# 05_USART.net
KiCad netlist of a schematic drawn in Altium Designer
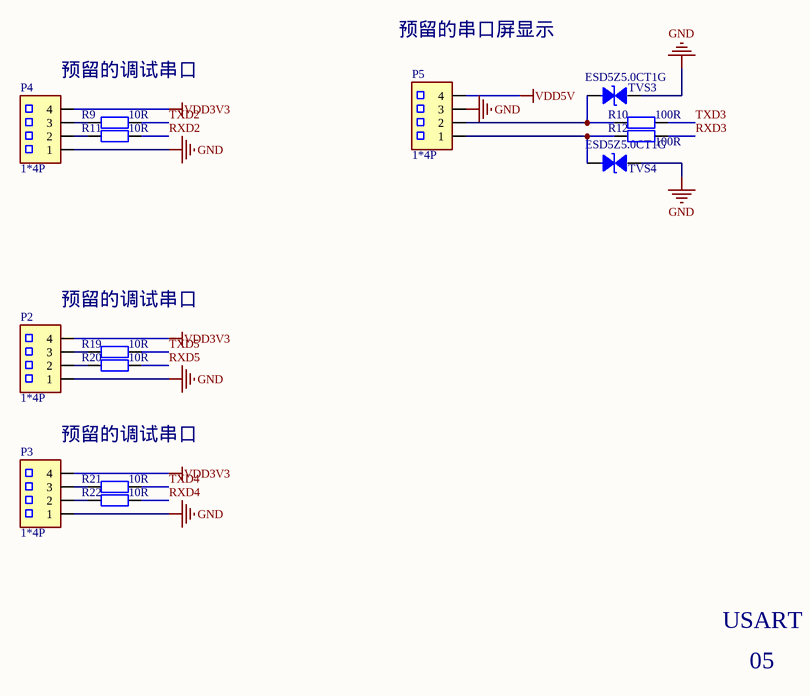
[diagram p0: 05_USART.SchDoc]

(export (version "E")
  (design (tool "Eeschema 10.0.6"))
  (components
    (comp (ref "P2") (value "1*4P") (footprint "XH2.54-4A") (libsource (lib "PARK-N5 V1.0") (part "HDR1*4")))
    (comp (ref "P3") (value "1*4P") (footprint "XH2.54-4A") (libsource (lib "PARK-N5 V1.0") (part "HDR1*4")))
    (comp (ref "P4") (value "1*4P") (footprint "XH2.54-4A") (libsource (lib "PARK-N5 V1.0") (part "HDR1*4")))
    (comp (ref "P5") (value "1*4P") (footprint "XH2.54-4A") (libsource (lib "PARK-N5 V1.0") (part "HDR1*4")))
    (comp (ref "R9")
      (value "10R")
      (footprint "SMD-0603")
      (description "贴片电阻 5%")
      (libsource (lib "XiaoyI") (part "RES2"))
    )
    (comp (ref "R10")
      (value "100R")
      (footprint "SMD-0603")
      (description "贴片电阻 5%")
      (libsource (lib "XiaoyI") (part "RES2"))
    )
    (comp (ref "R11")
      (value "10R")
      (footprint "SMD-0603")
      (description "贴片电阻 5%")
      (libsource (lib "XiaoyI") (part "RES2"))
    )
    (comp (ref "R12")
      (value "100R")
      (footprint "SMD-0603")
      (description "贴片电阻 5%")
      (libsource (lib "XiaoyI") (part "RES2"))
    )
    (comp (ref "R19")
      (value "10R")
      (footprint "SMD-0603")
      (description "贴片电阻 5%")
      (libsource (lib "XiaoyI") (part "RES2"))
    )
    (comp (ref "R20")
      (value "10R")
      (footprint "SMD-0603")
      (description "贴片电阻 5%")
      (libsource (lib "XiaoyI") (part "RES2"))
    )
    (comp (ref "R21")
      (value "10R")
      (footprint "SMD-0603")
      (description "贴片电阻 5%")
      (libsource (lib "XiaoyI") (part "RES2"))
    )
    (comp (ref "R22")
      (value "10R")
      (footprint "SMD-0603")
      (description "贴片电阻 5%")
      (libsource (lib "XiaoyI") (part "RES2"))
    )
    (comp (ref "TVS3")
      (value "ESD5Z5.0CT1G")
      (footprint "SOD-523")
      (description "TVS")
      (libsource (lib "XiaoyI") (part "TVS-1"))
    )
    (comp (ref "TVS4")
      (value "ESD5Z5.0CT1G")
      (footprint "SOD-523")
      (description "TVS")
      (libsource (lib "XiaoyI") (part "TVS-1"))
    )
  )
  (nets
    (net (code "1") (name "/RXD2") (class "Default")
      (node (ref "R11") (pin "2") (pinfunction "2_2") (pintype "passive"))
    )
    (net (code "2") (name "/RXD3") (class "Default")
      (node (ref "R12") (pin "2") (pinfunction "2_2") (pintype "passive"))
    )
    (net (code "3") (name "/RXD4") (class "Default")
      (node (ref "R22") (pin "2") (pinfunction "2_2") (pintype "passive"))
    )
    (net (code "4") (name "/RXD5") (class "Default")
      (node (ref "R20") (pin "2") (pinfunction "2_2") (pintype "passive"))
    )
    (net (code "5") (name "/TXD2") (class "Default")
      (node (ref "R9") (pin "2") (pinfunction "2_2") (pintype "passive"))
    )
    (net (code "6") (name "/TXD3") (class "Default")
      (node (ref "R10") (pin "2") (pinfunction "2_2") (pintype "passive"))
    )
    (net (code "7") (name "/TXD4") (class "Default")
      (node (ref "R21") (pin "2") (pinfunction "2_2") (pintype "passive"))
    )
    (net (code "8") (name "/TXD5") (class "Default")
      (node (ref "R19") (pin "2") (pinfunction "2_2") (pintype "passive"))
    )
    (net (code "9") (name "GND") (class "Default")
      (node (ref "P2") (pin "1") (pinfunction "1_1") (pintype "passive"))
      (node (ref "P3") (pin "1") (pinfunction "1_1") (pintype "passive"))
      (node (ref "P4") (pin "1") (pinfunction "1_1") (pintype "passive"))
      (node (ref "P5") (pin "3") (pinfunction "3_3") (pintype "passive"))
      (node (ref "TVS3") (pin "1") (pinfunction "A_1") (pintype "passive"))
      (node (ref "TVS4") (pin "1") (pinfunction "A_1") (pintype "passive"))
    )
    (net (code "10") (name "Net-(P2-Pad2)") (class "Default")
      (node (ref "P2") (pin "2") (pinfunction "2_2") (pintype "passive"))
      (node (ref "R20") (pin "1") (pinfunction "1_1") (pintype "passive"))
    )
    (net (code "11") (name "Net-(P2-Pad3)") (class "Default")
      (node (ref "P2") (pin "3") (pinfunction "3_3") (pintype "passive"))
      (node (ref "R19") (pin "1") (pinfunction "1_1") (pintype "passive"))
    )
    (net (code "12") (name "Net-(P3-Pad2)") (class "Default")
      (node (ref "P3") (pin "2") (pinfunction "2_2") (pintype "passive"))
      (node (ref "R22") (pin "1") (pinfunction "1_1") (pintype "passive"))
    )
    (net (code "13") (name "Net-(P3-Pad3)") (class "Default")
      (node (ref "P3") (pin "3") (pinfunction "3_3") (pintype "passive"))
      (node (ref "R21") (pin "1") (pinfunction "1_1") (pintype "passive"))
    )
    (net (code "14") (name "Net-(P4-Pad2)") (class "Default")
      (node (ref "P4") (pin "2") (pinfunction "2_2") (pintype "passive"))
      (node (ref "R11") (pin "1") (pinfunction "1_1") (pintype "passive"))
    )
    (net (code "15") (name "Net-(P4-Pad3)") (class "Default")
      (node (ref "P4") (pin "3") (pinfunction "3_3") (pintype "passive"))
      (node (ref "R9") (pin "1") (pinfunction "1_1") (pintype "passive"))
    )
    (net (code "16") (name "Net-(TVS3-B)") (class "Default")
      (node (ref "P5") (pin "2") (pinfunction "2_2") (pintype "passive"))
      (node (ref "R10") (pin "1") (pinfunction "1_1") (pintype "passive"))
      (node (ref "TVS3") (pin "2") (pinfunction "B_2") (pintype "passive"))
    )
    (net (code "17") (name "Net-(TVS4-B)") (class "Default")
      (node (ref "P5") (pin "1") (pinfunction "1_1") (pintype "passive"))
      (node (ref "R12") (pin "1") (pinfunction "1_1") (pintype "passive"))
      (node (ref "TVS4") (pin "2") (pinfunction "B_2") (pintype "passive"))
    )
    (net (code "18") (name "VDD3V3") (class "Default")
      (node (ref "P2") (pin "4") (pinfunction "4_4") (pintype "passive"))
      (node (ref "P3") (pin "4") (pinfunction "4_4") (pintype "passive"))
      (node (ref "P4") (pin "4") (pinfunction "4_4") (pintype "passive"))
    )
    (net (code "19") (name "VDD5V") (class "Default")
      (node (ref "P5") (pin "4") (pinfunction "4_4") (pintype "passive"))
    )
  )
)
